# motor_voltage.net
KiCad netlist of a schematic drawn in Altium Designer
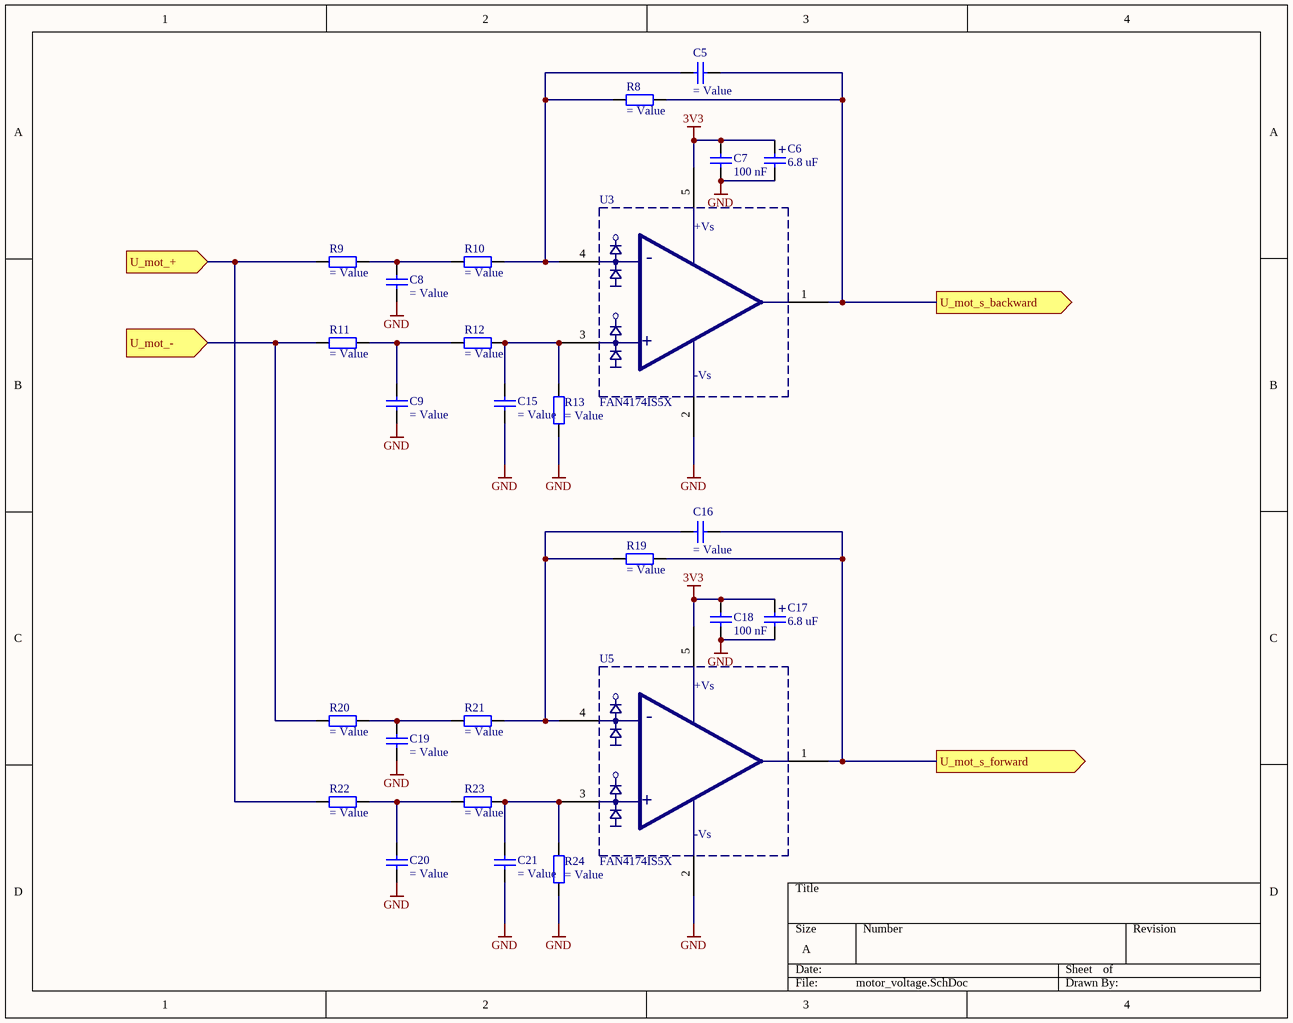
[diagram p0: motor_voltage.SchDoc]

(export (version "E")
  (design (tool "Eeschema 10.0.6"))
  (components
    (comp (ref "C5") (value "~") (footprint "0805_C") (libsource (lib "PJ") (part "CAP 0805")))
    (comp (ref "C6")
      (value "6.8 uF")
      (description "SMD Aluminium Electrolytic Capacitor, Radial Can - SMD, 6.8 µF, 35 V, WCAP-ASLI Series")
      (libsource (lib "PJ") (part "CAP ELKO SMD"))
    )
    (comp (ref "C7") (value "100 nF") (footprint "0805_C") (libsource (lib "PJ") (part "CAP 0805")))
    (comp (ref "C8") (value "~") (footprint "0805_C") (libsource (lib "PJ") (part "CAP 0805")))
    (comp (ref "C9") (value "~") (footprint "0805_C") (libsource (lib "PJ") (part "CAP 0805")))
    (comp (ref "C15") (value "~") (footprint "0805_C") (libsource (lib "PJ") (part "CAP 0805")))
    (comp (ref "C16") (value "~") (footprint "0805_C") (libsource (lib "PJ") (part "CAP 0805")))
    (comp (ref "C17")
      (value "6.8 uF")
      (description "SMD Aluminium Electrolytic Capacitor, Radial Can - SMD, 6.8 µF, 35 V, WCAP-ASLI Series")
      (libsource (lib "PJ") (part "CAP ELKO SMD"))
    )
    (comp (ref "C18") (value "100 nF") (footprint "0805_C") (libsource (lib "PJ") (part "CAP 0805")))
    (comp (ref "C19") (value "~") (footprint "0805_C") (libsource (lib "PJ") (part "CAP 0805")))
    (comp (ref "C20") (value "~") (footprint "0805_C") (libsource (lib "PJ") (part "CAP 0805")))
    (comp (ref "C21") (value "~") (footprint "0805_C") (libsource (lib "PJ") (part "CAP 0805")))
    (comp (ref "R8") (value "~") (libsource (lib "PJ") (part "RES 0805")))
    (comp (ref "R9") (value "~") (libsource (lib "PJ") (part "RES 0805")))
    (comp (ref "R10") (value "~") (libsource (lib "PJ") (part "RES 0805")))
    (comp (ref "R11") (value "~") (libsource (lib "PJ") (part "RES 0805")))
    (comp (ref "R12") (value "~") (libsource (lib "PJ") (part "RES 0805")))
    (comp (ref "R13") (value "~") (libsource (lib "") (part "RES 0805_1")))
    (comp (ref "R19") (value "~") (libsource (lib "PJ") (part "RES 0805")))
    (comp (ref "R20") (value "~") (libsource (lib "PJ") (part "RES 0805")))
    (comp (ref "R21") (value "~") (libsource (lib "PJ") (part "RES 0805")))
    (comp (ref "R22") (value "~") (libsource (lib "PJ") (part "RES 0805")))
    (comp (ref "R23") (value "~") (libsource (lib "PJ") (part "RES 0805")))
    (comp (ref "R24") (value "~") (libsource (lib "") (part "RES 0805_1")))
    (comp (ref "U3") (value "FAN4174IS5X") (footprint "SOT-23-5") (libsource (lib "PJ") (part "FAN4174IS5X")))
    (comp (ref "U5") (value "FAN4174IS5X") (footprint "SOT-23-5") (libsource (lib "PJ") (part "FAN4174IS5X")))
  )
  (nets
    (net (code "1") (name "/U_mot_+") (class "Default")
      (node (ref "R22") (pin "1") (pinfunction "1_1") (pintype "passive"))
      (node (ref "R9") (pin "1") (pinfunction "1_1") (pintype "passive"))
    )
    (net (code "2") (name "/U_mot_-") (class "Default")
      (node (ref "R11") (pin "1") (pinfunction "1_1") (pintype "passive"))
      (node (ref "R20") (pin "1") (pinfunction "1_1") (pintype "passive"))
    )
    (net (code "3") (name "/U_mot_s_backward") (class "Default")
      (node (ref "C5") (pin "2") (pinfunction "2_2") (pintype "passive"))
      (node (ref "R8") (pin "2") (pinfunction "2_2") (pintype "passive"))
      (node (ref "U3") (pin "1") (pinfunction "OUT_1") (pintype "passive"))
    )
    (net (code "4") (name "/U_mot_s_forward") (class "Default")
      (node (ref "C16") (pin "2") (pinfunction "2_2") (pintype "passive"))
      (node (ref "R19") (pin "2") (pinfunction "2_2") (pintype "passive"))
      (node (ref "U5") (pin "1") (pinfunction "OUT_1") (pintype "passive"))
    )
    (net (code "5") (name "3V3") (class "Default")
      (node (ref "C17") (pin "2") (pinfunction "2_2") (pintype "passive"))
      (node (ref "C18") (pin "1") (pinfunction "1_1") (pintype "passive"))
      (node (ref "C6") (pin "2") (pinfunction "2_2") (pintype "passive"))
      (node (ref "C7") (pin "1") (pinfunction "1_1") (pintype "passive"))
      (node (ref "U3") (pin "5") (pinfunction "+Vs_5") (pintype "passive"))
      (node (ref "U5") (pin "5") (pinfunction "+Vs_5") (pintype "passive"))
    )
    (net (code "6") (name "GND") (class "Default")
      (node (ref "C15") (pin "2") (pinfunction "2_2") (pintype "passive"))
      (node (ref "C17") (pin "1") (pinfunction "1_1") (pintype "passive"))
      (node (ref "C18") (pin "2") (pinfunction "2_2") (pintype "passive"))
      (node (ref "C19") (pin "2") (pinfunction "2_2") (pintype "passive"))
      (node (ref "C20") (pin "2") (pinfunction "2_2") (pintype "passive"))
      (node (ref "C21") (pin "2") (pinfunction "2_2") (pintype "passive"))
      (node (ref "C6") (pin "1") (pinfunction "1_1") (pintype "passive"))
      (node (ref "C7") (pin "2") (pinfunction "2_2") (pintype "passive"))
      (node (ref "C8") (pin "2") (pinfunction "2_2") (pintype "passive"))
      (node (ref "C9") (pin "2") (pinfunction "2_2") (pintype "passive"))
      (node (ref "R13") (pin "1") (pinfunction "1_1") (pintype "passive"))
      (node (ref "R24") (pin "1") (pinfunction "1_1") (pintype "passive"))
      (node (ref "U3") (pin "2") (pinfunction "-Vs_2") (pintype "passive"))
      (node (ref "U5") (pin "2") (pinfunction "-Vs_2") (pintype "passive"))
    )
    (net (code "7") (name "Net-(C8-Pad1)") (class "Default")
      (node (ref "C8") (pin "1") (pinfunction "1_1") (pintype "passive"))
      (node (ref "R10") (pin "1") (pinfunction "1_1") (pintype "passive"))
      (node (ref "R9") (pin "2") (pinfunction "2_2") (pintype "passive"))
    )
    (net (code "8") (name "Net-(C9-Pad1)") (class "Default")
      (node (ref "C9") (pin "1") (pinfunction "1_1") (pintype "passive"))
      (node (ref "R11") (pin "2") (pinfunction "2_2") (pintype "passive"))
      (node (ref "R12") (pin "1") (pinfunction "1_1") (pintype "passive"))
    )
    (net (code "9") (name "Net-(C19-Pad1)") (class "Default")
      (node (ref "C19") (pin "1") (pinfunction "1_1") (pintype "passive"))
      (node (ref "R20") (pin "2") (pinfunction "2_2") (pintype "passive"))
      (node (ref "R21") (pin "1") (pinfunction "1_1") (pintype "passive"))
    )
    (net (code "10") (name "Net-(C20-Pad1)") (class "Default")
      (node (ref "C20") (pin "1") (pinfunction "1_1") (pintype "passive"))
      (node (ref "R22") (pin "2") (pinfunction "2_2") (pintype "passive"))
      (node (ref "R23") (pin "1") (pinfunction "1_1") (pintype "passive"))
    )
    (net (code "11") (name "Net-(U3-+IN)") (class "Default")
      (node (ref "C15") (pin "1") (pinfunction "1_1") (pintype "passive"))
      (node (ref "R12") (pin "2") (pinfunction "2_2") (pintype "passive"))
      (node (ref "R13") (pin "2") (pinfunction "2_2") (pintype "passive"))
      (node (ref "U3") (pin "3") (pinfunction "+IN_3") (pintype "passive"))
    )
    (net (code "12") (name "Net-(U3--IN)") (class "Default")
      (node (ref "C5") (pin "1") (pinfunction "1_1") (pintype "passive"))
      (node (ref "R10") (pin "2") (pinfunction "2_2") (pintype "passive"))
      (node (ref "R8") (pin "1") (pinfunction "1_1") (pintype "passive"))
      (node (ref "U3") (pin "4") (pinfunction "-IN_4") (pintype "passive"))
    )
    (net (code "13") (name "Net-(U5-+IN)") (class "Default")
      (node (ref "C21") (pin "1") (pinfunction "1_1") (pintype "passive"))
      (node (ref "R23") (pin "2") (pinfunction "2_2") (pintype "passive"))
      (node (ref "R24") (pin "2") (pinfunction "2_2") (pintype "passive"))
      (node (ref "U5") (pin "3") (pinfunction "+IN_3") (pintype "passive"))
    )
    (net (code "14") (name "Net-(U5--IN)") (class "Default")
      (node (ref "C16") (pin "1") (pinfunction "1_1") (pintype "passive"))
      (node (ref "R19") (pin "1") (pinfunction "1_1") (pintype "passive"))
      (node (ref "R21") (pin "2") (pinfunction "2_2") (pintype "passive"))
      (node (ref "U5") (pin "4") (pinfunction "-IN_4") (pintype "passive"))
    )
  )
)
